# Discrete_3V3_Linear_Regulator.net
KiCad netlist of a schematic drawn in Altium Designer
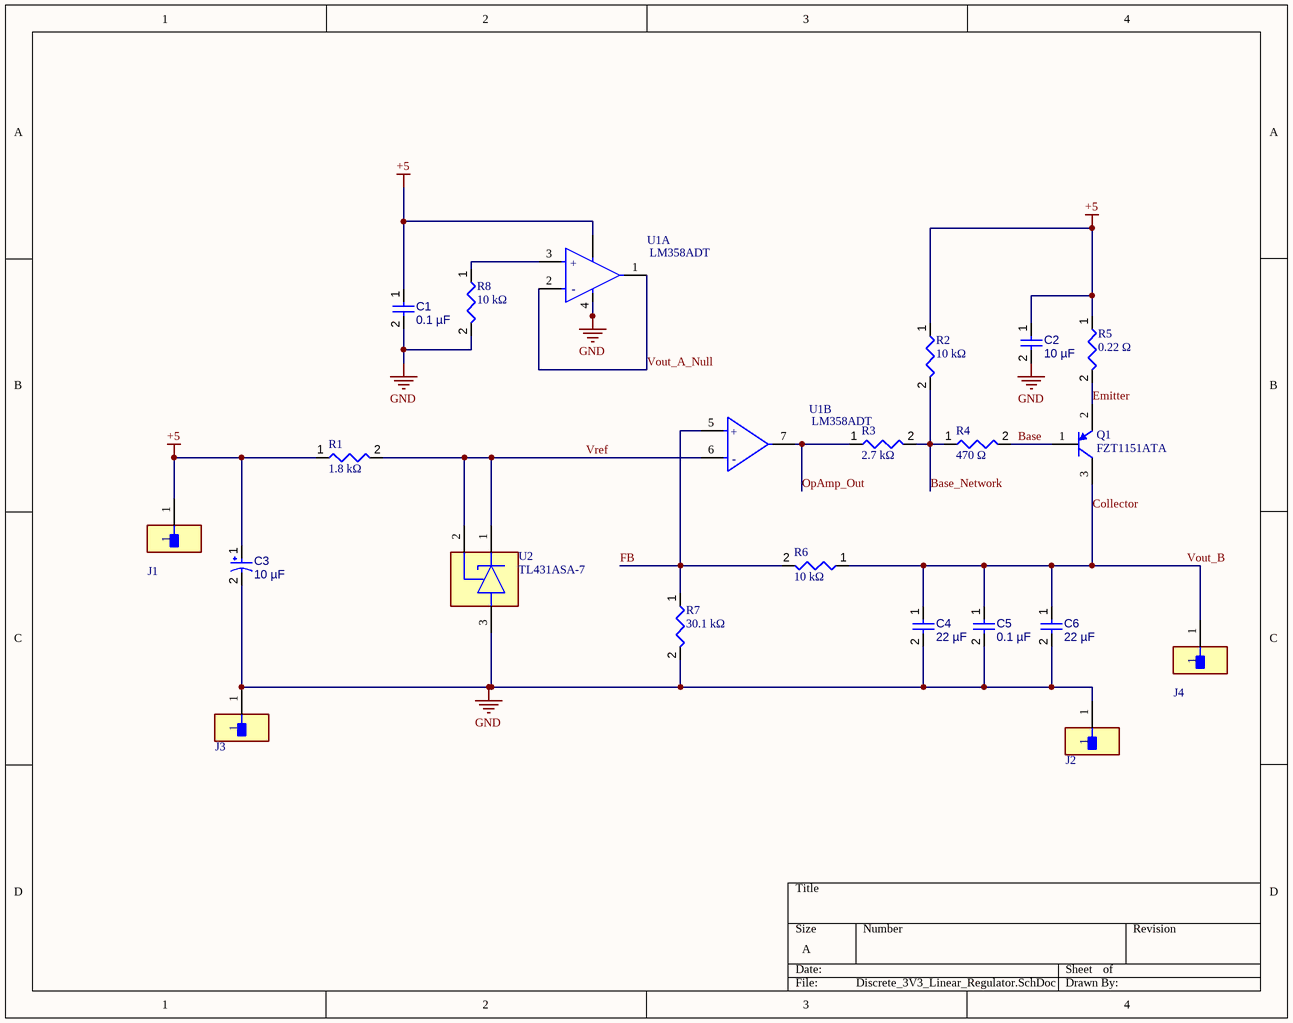
[diagram p0: Discrete_3V3_Linear_Regulator.SchDoc]

(export (version "E")
  (design (tool "Eeschema 10.0.6"))
  (components
    (comp (ref "C1")
      (value "0.1 µF")
      (footprint "CAP_0805_IPC_M")
      (description "Generic non-polarized capacitor (ceramic/film), value defined per instance")
      (libsource (lib "Standard_Passives") (part "C"))
    )
    (comp (ref "C2")
      (value "10 µF")
      (footprint "CAP_0805_IPC_M")
      (description "Generic non-polarized capacitor (ceramic/film), value defined per instance")
      (libsource (lib "Standard_Passives") (part "C"))
    )
    (comp (ref "C3")
      (value "10 µF")
      (footprint "Components - 29.12.25 - 21.02:WCAP-PSLP_D5H5.5")
      (description "WCAP-PSLP Radial Can - SMD Aluminum Polymer Capacitor 0.197Dia 5.00mm ±20% 100muF 10V")
      (fields
        (field (name "MANUFACTURER") "Wurth Elektronik")
        (field (name "MANUFACTURER PART NUMBER") "875105242010")
      )
      (libsource (lib "Standard_Passives") (part "C_POL"))
    )
    (comp (ref "C4")
      (value "22 µF")
      (footprint "CAP_0805_IPC_M")
      (description "Generic non-polarized capacitor (ceramic/film), value defined per instance")
      (libsource (lib "Standard_Passives") (part "C"))
    )
    (comp (ref "C5")
      (value "0.1 µF")
      (footprint "CAP_0805_IPC_M")
      (description "Generic non-polarized capacitor (ceramic/film), value defined per instance")
      (libsource (lib "Standard_Passives") (part "C"))
    )
    (comp (ref "C6")
      (value "22 µF")
      (footprint "CAP_0805_IPC_M")
      (description "Adjustable based on output requirements")
      (libsource (lib "Standard_Passives") (part "C"))
    )
    (comp (ref "J1")
      (value "HTSW-101-07-L-S")
      (footprint "FP-HTSW-101-07-L-S-MFG")
      (description "CONN HEADER VERT 1POS")
      (libsource (lib "Altium Content Vault") (part "dd45045ce8184df9e99e12baf3f412c"))
    )
    (comp (ref "J2")
      (value "HTSW-101-07-L-S")
      (footprint "FP-HTSW-101-07-L-S-MFG")
      (description "CONN HEADER VERT 1POS")
      (libsource (lib "Altium Content Vault") (part "dd45045ce8184df9e99e12baf3f412c"))
    )
    (comp (ref "J3")
      (value "HTSW-101-07-L-S")
      (footprint "FP-HTSW-101-07-L-S-MFG")
      (description "CONN HEADER VERT 1POS")
      (libsource (lib "Altium Content Vault") (part "dd45045ce8184df9e99e12baf3f412c"))
    )
    (comp (ref "J4")
      (value "HTSW-101-07-L-S")
      (footprint "FP-HTSW-101-07-L-S-MFG")
      (description "CONN HEADER VERT 1POS")
      (libsource (lib "Altium Content Vault") (part "dd45045ce8184df9e99e12baf3f412c"))
    )
    (comp (ref "Q1")
      (value "FZT1151ATA")
      (footprint "SOT223_4P_TAB_IPC_L")
      (description "Generic PNP BJT transistor symbol (discrete)")
      (libsource (lib "Discrete_Actives") (part "BJT_PNP"))
    )
    (comp (ref "R1")
      (value "1.8 kΩ")
      (footprint "RES_0805_IPC_M")
      (description "Generic resistor, value defined per instance")
      (libsource (lib "Standard_Passives") (part "R"))
    )
    (comp (ref "R2")
      (value "10 kΩ")
      (footprint "RES_0805_IPC_M")
      (description "Generic resistor, value defined per instance")
      (libsource (lib "Standard_Passives") (part "R"))
    )
    (comp (ref "R3")
      (value "2.7 kΩ")
      (footprint "RES_0805_IPC_M")
      (description "Generic resistor, value defined per instance")
      (libsource (lib "Standard_Passives") (part "R"))
    )
    (comp (ref "R4")
      (value "470 Ω")
      (footprint "RES_0805_IPC_M")
      (description "Generic resistor, value defined per instance")
      (libsource (lib "Standard_Passives") (part "R"))
    )
    (comp (ref "R5")
      (value "0.22 Ω")
      (footprint "RES_1206_IPC_M")
      (description "Generic resistor, value defined per instance")
      (libsource (lib "Standard_Passives") (part "R"))
    )
    (comp (ref "R6")
      (value "10 kΩ")
      (footprint "RES_0805_IPC_M")
      (description "Generic resistor, value defined per instance")
      (libsource (lib "Standard_Passives") (part "R"))
    )
    (comp (ref "R7")
      (value "30.1 kΩ")
      (footprint "RES_0805_IPC_M")
      (description "Generic resistor, value defined per instance")
      (libsource (lib "Standard_Passives") (part "R"))
    )
    (comp (ref "R8")
      (value "10 kΩ")
      (footprint "RES_0805_IPC_M")
      (description "Generic resistor, value defined per instance")
      (libsource (lib "Standard_Passives") (part "R"))
    )
    (comp (ref "U1")
      (value "LM358ADT")
      (footprint "FP-SO8-IPC_A")
      (description "IC OPAMP GP 2 CIRCUIT 8SO")
      (fields
        (field (name "MANUFACTURER") "STMicroelectronics")
        (field (name "OCTOPART") "https://octopart.com/lm358adt-stmicroelectronics-410420")
      )
      (libsource (lib "Altium Content Vault") (part "9f386d5a0a155305257da89b0c2f71e"))
    )
    (comp (ref "U2")
      (value "TL431ASA-7")
      (footprint "FP-SOT23-MFG")
      (description "IC VREF SHUNT ADJ SOT23-3")
      (fields
        (field (name "OCTOPART") "https://octopart.com/tl431asa-7-diodes+inc.-18832779")
        (field (name "MANUFACTURER") "DIODES INC.")
      )
      (libsource (lib "Altium Content Vault") (part "bb7a1bf3cd7629b94a2ffd22ed0b9f9"))
    )
  )
  (nets
    (net (code "1") (name "+5") (class "Default")
      (node (ref "C1") (pin "1") (pinfunction "1_1") (pintype "passive"))
      (node (ref "C2") (pin "1") (pinfunction "1_1") (pintype "passive"))
      (node (ref "C3") (pin "1") (pinfunction "1_1") (pintype "passive"))
      (node (ref "J1") (pin "1") (pinfunction "1_1") (pintype "passive"))
      (node (ref "R1") (pin "1") (pinfunction "1_1") (pintype "passive"))
      (node (ref "R2") (pin "1") (pinfunction "1_1") (pintype "passive"))
      (node (ref "R5") (pin "1") (pinfunction "1_1") (pintype "passive"))
      (node (ref "U1") (pin "8") (pinfunction "VCC+_8") (pintype "power_in"))
    )
    (net (code "2") (name "/Base") (class "Default")
      (node (ref "Q1") (pin "1") (pinfunction "B_1") (pintype "passive"))
      (node (ref "R4") (pin "2") (pinfunction "2_2") (pintype "passive"))
    )
    (net (code "3") (name "/Base_Network") (class "Default")
      (node (ref "R2") (pin "2") (pinfunction "2_2") (pintype "passive"))
      (node (ref "R3") (pin "2") (pinfunction "2_2") (pintype "passive"))
      (node (ref "R4") (pin "1") (pinfunction "1_1") (pintype "passive"))
    )
    (net (code "4") (name "/Collector") (class "Default")
      (node (ref "C4") (pin "1") (pinfunction "1_1") (pintype "passive"))
      (node (ref "C5") (pin "1") (pinfunction "1_1") (pintype "passive"))
      (node (ref "C6") (pin "1") (pinfunction "1_1") (pintype "passive"))
      (node (ref "J4") (pin "1") (pinfunction "1_1") (pintype "passive"))
      (node (ref "Q1") (pin "3") (pinfunction "C_3") (pintype "passive"))
      (node (ref "R6") (pin "1") (pinfunction "1_1") (pintype "passive"))
    )
    (net (code "5") (name "/Emitter") (class "Default")
      (node (ref "Q1") (pin "2") (pinfunction "E_2") (pintype "passive"))
      (node (ref "R5") (pin "2") (pinfunction "2_2") (pintype "passive"))
    )
    (net (code "6") (name "/FB") (class "Default")
      (node (ref "R6") (pin "2") (pinfunction "2_2") (pintype "passive"))
      (node (ref "R7") (pin "1") (pinfunction "1_1") (pintype "passive"))
      (node (ref "U1") (pin "5") (pinfunction "In2+_5") (pintype "tri_state"))
    )
    (net (code "7") (name "/OpAmp_Out") (class "Default")
      (node (ref "R3") (pin "1") (pinfunction "1_1") (pintype "passive"))
      (node (ref "U1") (pin "7") (pinfunction "Out2_7") (pintype "passive"))
    )
    (net (code "8") (name "/Vout_A_Null") (class "Default")
      (node (ref "U1") (pin "1") (pinfunction "Out1_1") (pintype "passive"))
      (node (ref "U1") (pin "2") (pinfunction "In1-_2") (pintype "tri_state"))
    )
    (net (code "9") (name "/Vref") (class "Default")
      (node (ref "R1") (pin "2") (pinfunction "2_2") (pintype "passive"))
      (node (ref "U1") (pin "6") (pinfunction "In2-_6") (pintype "tri_state"))
      (node (ref "U2") (pin "1") (pinfunction "C_1") (pintype "passive"))
      (node (ref "U2") (pin "2") (pinfunction "REF_2") (pintype "passive"))
    )
    (net (code "10") (name "GND") (class "Default")
      (node (ref "C1") (pin "2") (pinfunction "2_2") (pintype "passive"))
      (node (ref "C2") (pin "2") (pinfunction "2_2") (pintype "passive"))
      (node (ref "C3") (pin "2") (pinfunction "2_2") (pintype "passive"))
      (node (ref "C4") (pin "2") (pinfunction "2_2") (pintype "passive"))
      (node (ref "C5") (pin "2") (pinfunction "2_2") (pintype "passive"))
      (node (ref "C6") (pin "2") (pinfunction "2_2") (pintype "passive"))
      (node (ref "J2") (pin "1") (pinfunction "1_1") (pintype "passive"))
      (node (ref "J3") (pin "1") (pinfunction "1_1") (pintype "passive"))
      (node (ref "R7") (pin "2") (pinfunction "2_2") (pintype "passive"))
      (node (ref "R8") (pin "2") (pinfunction "2_2") (pintype "passive"))
      (node (ref "U1") (pin "4") (pinfunction "VCC-_4") (pintype "power_in"))
      (node (ref "U2") (pin "3") (pinfunction "A_3") (pintype "passive"))
    )
    (net (code "11") (name "Net-(U1A-In1+)") (class "Default")
      (node (ref "R8") (pin "1") (pinfunction "1_1") (pintype "passive"))
      (node (ref "U1") (pin "3") (pinfunction "In1+_3") (pintype "tri_state"))
    )
  )
)
